# CN-Cape004.net
KiCad netlist of a schematic drawn in EAGLE
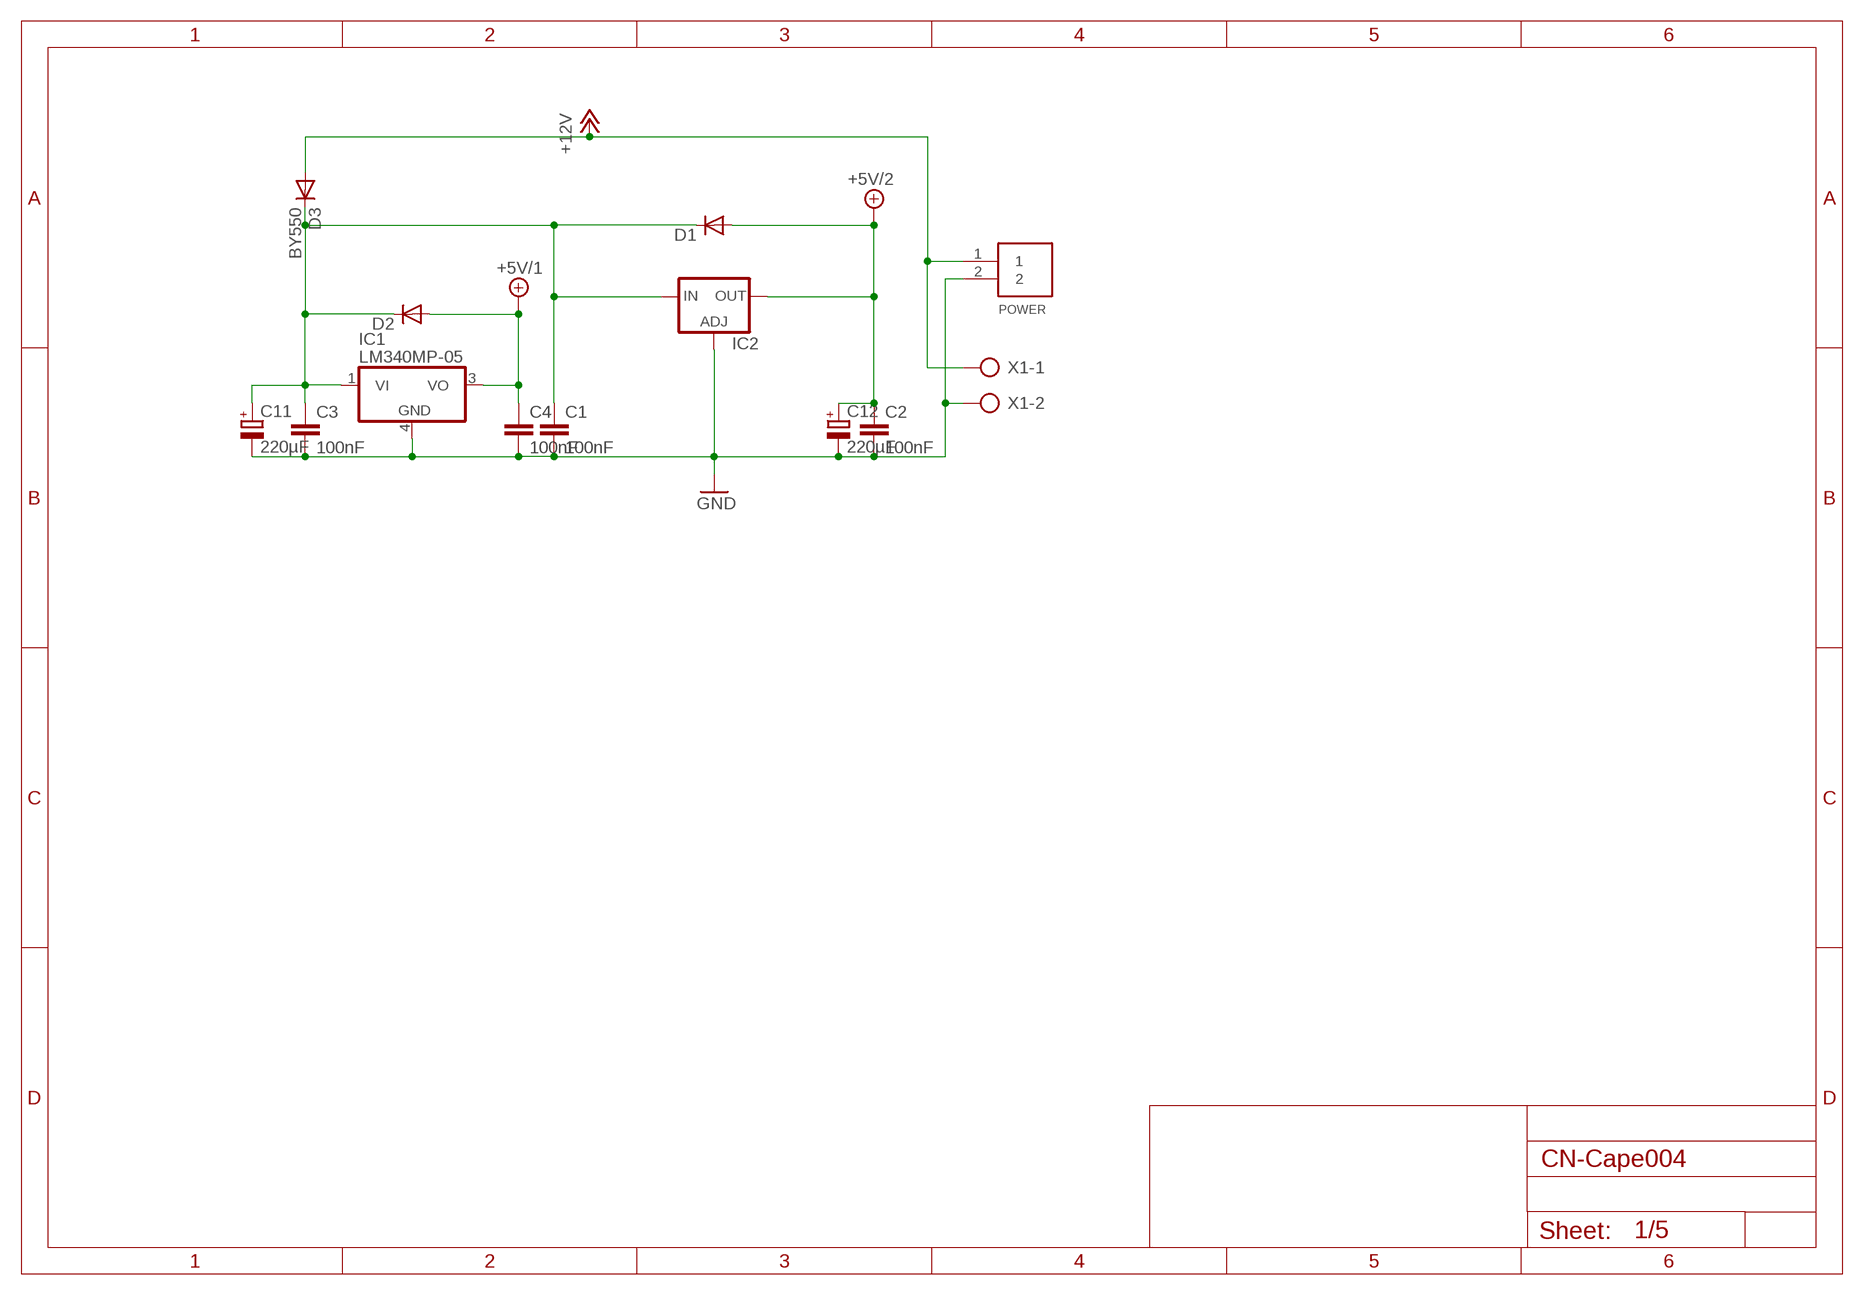
[diagram p0: schematic, sheet 1]
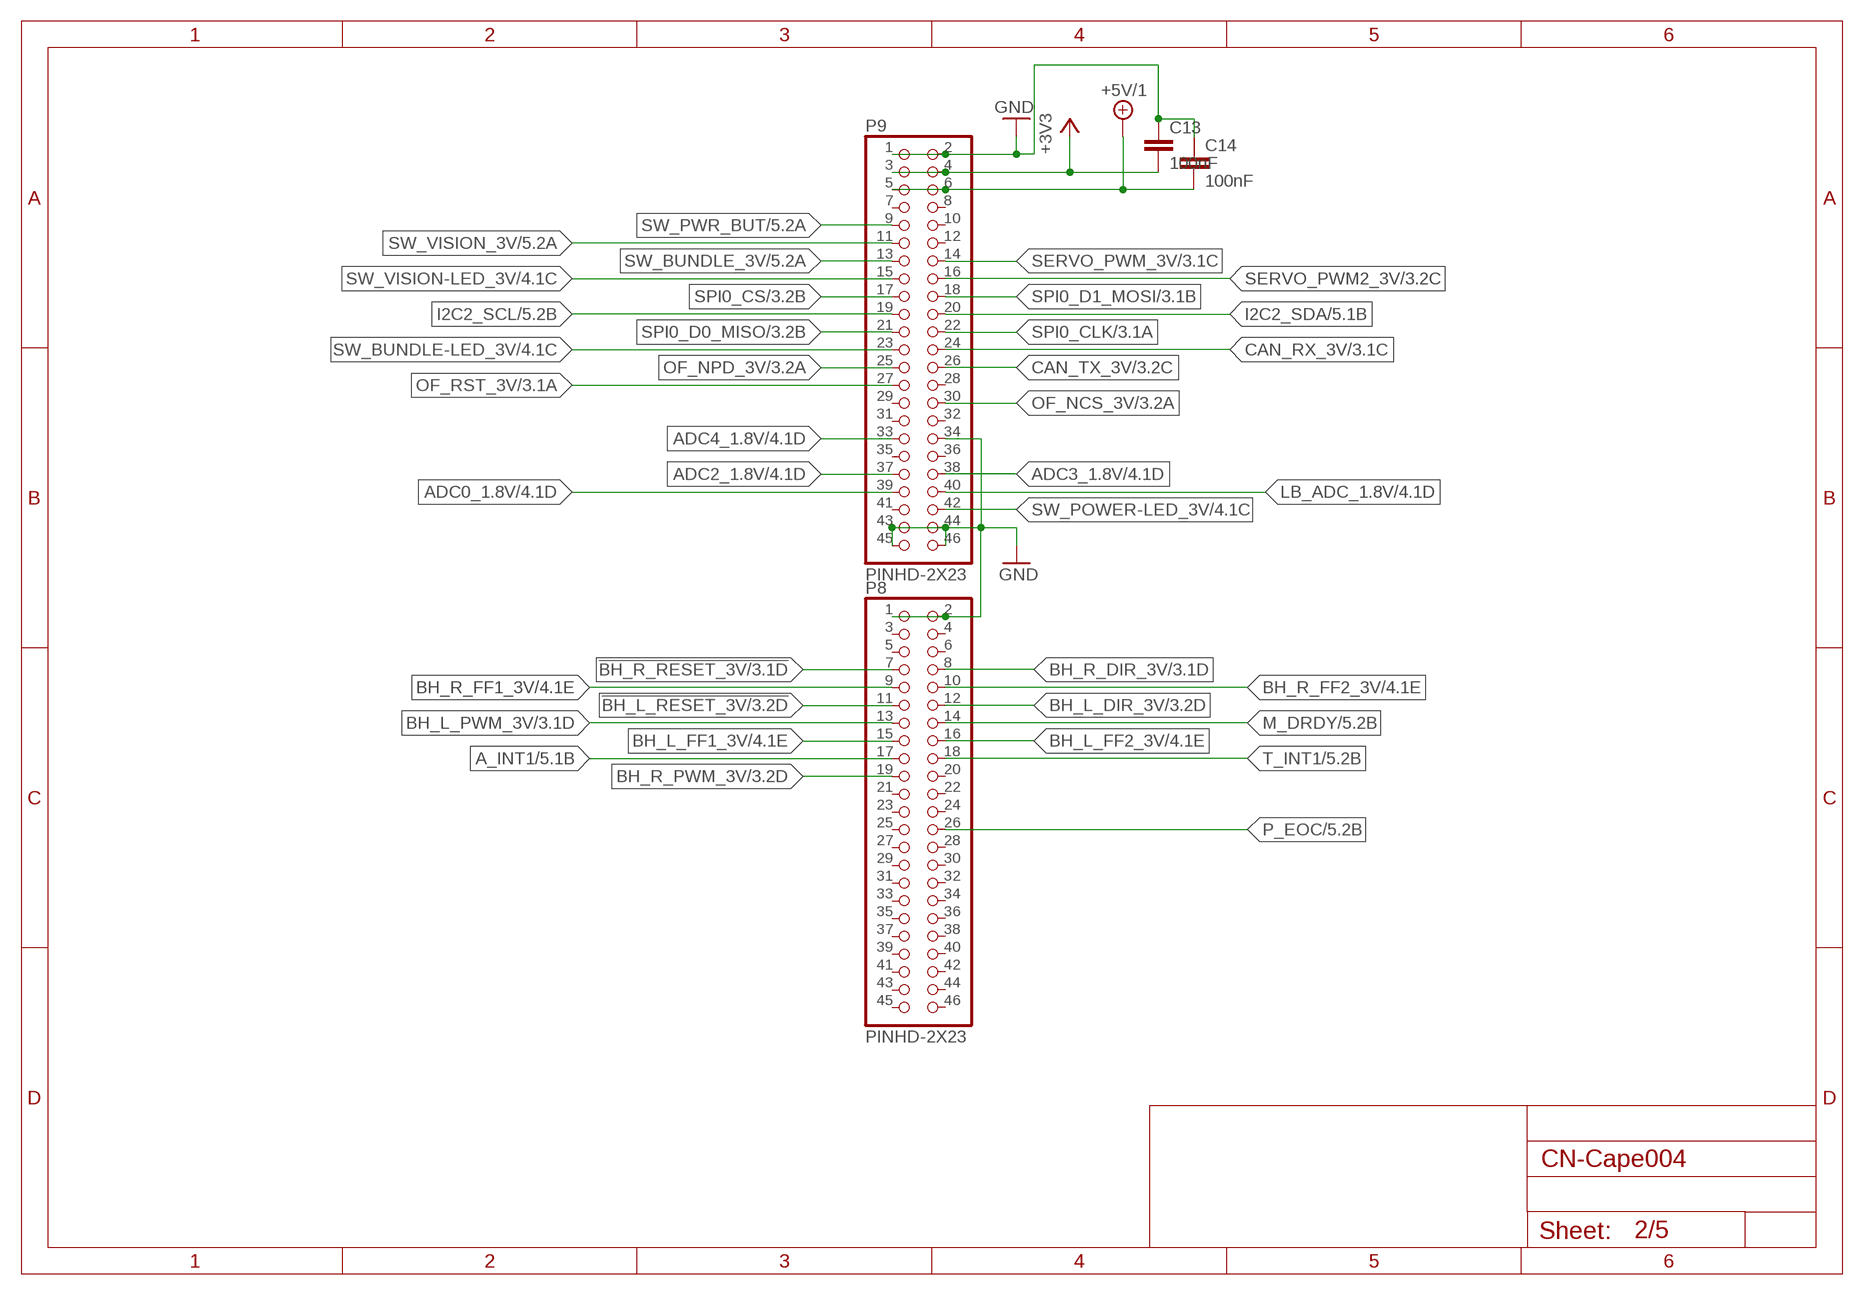
[diagram p1: schematic, sheet 2]
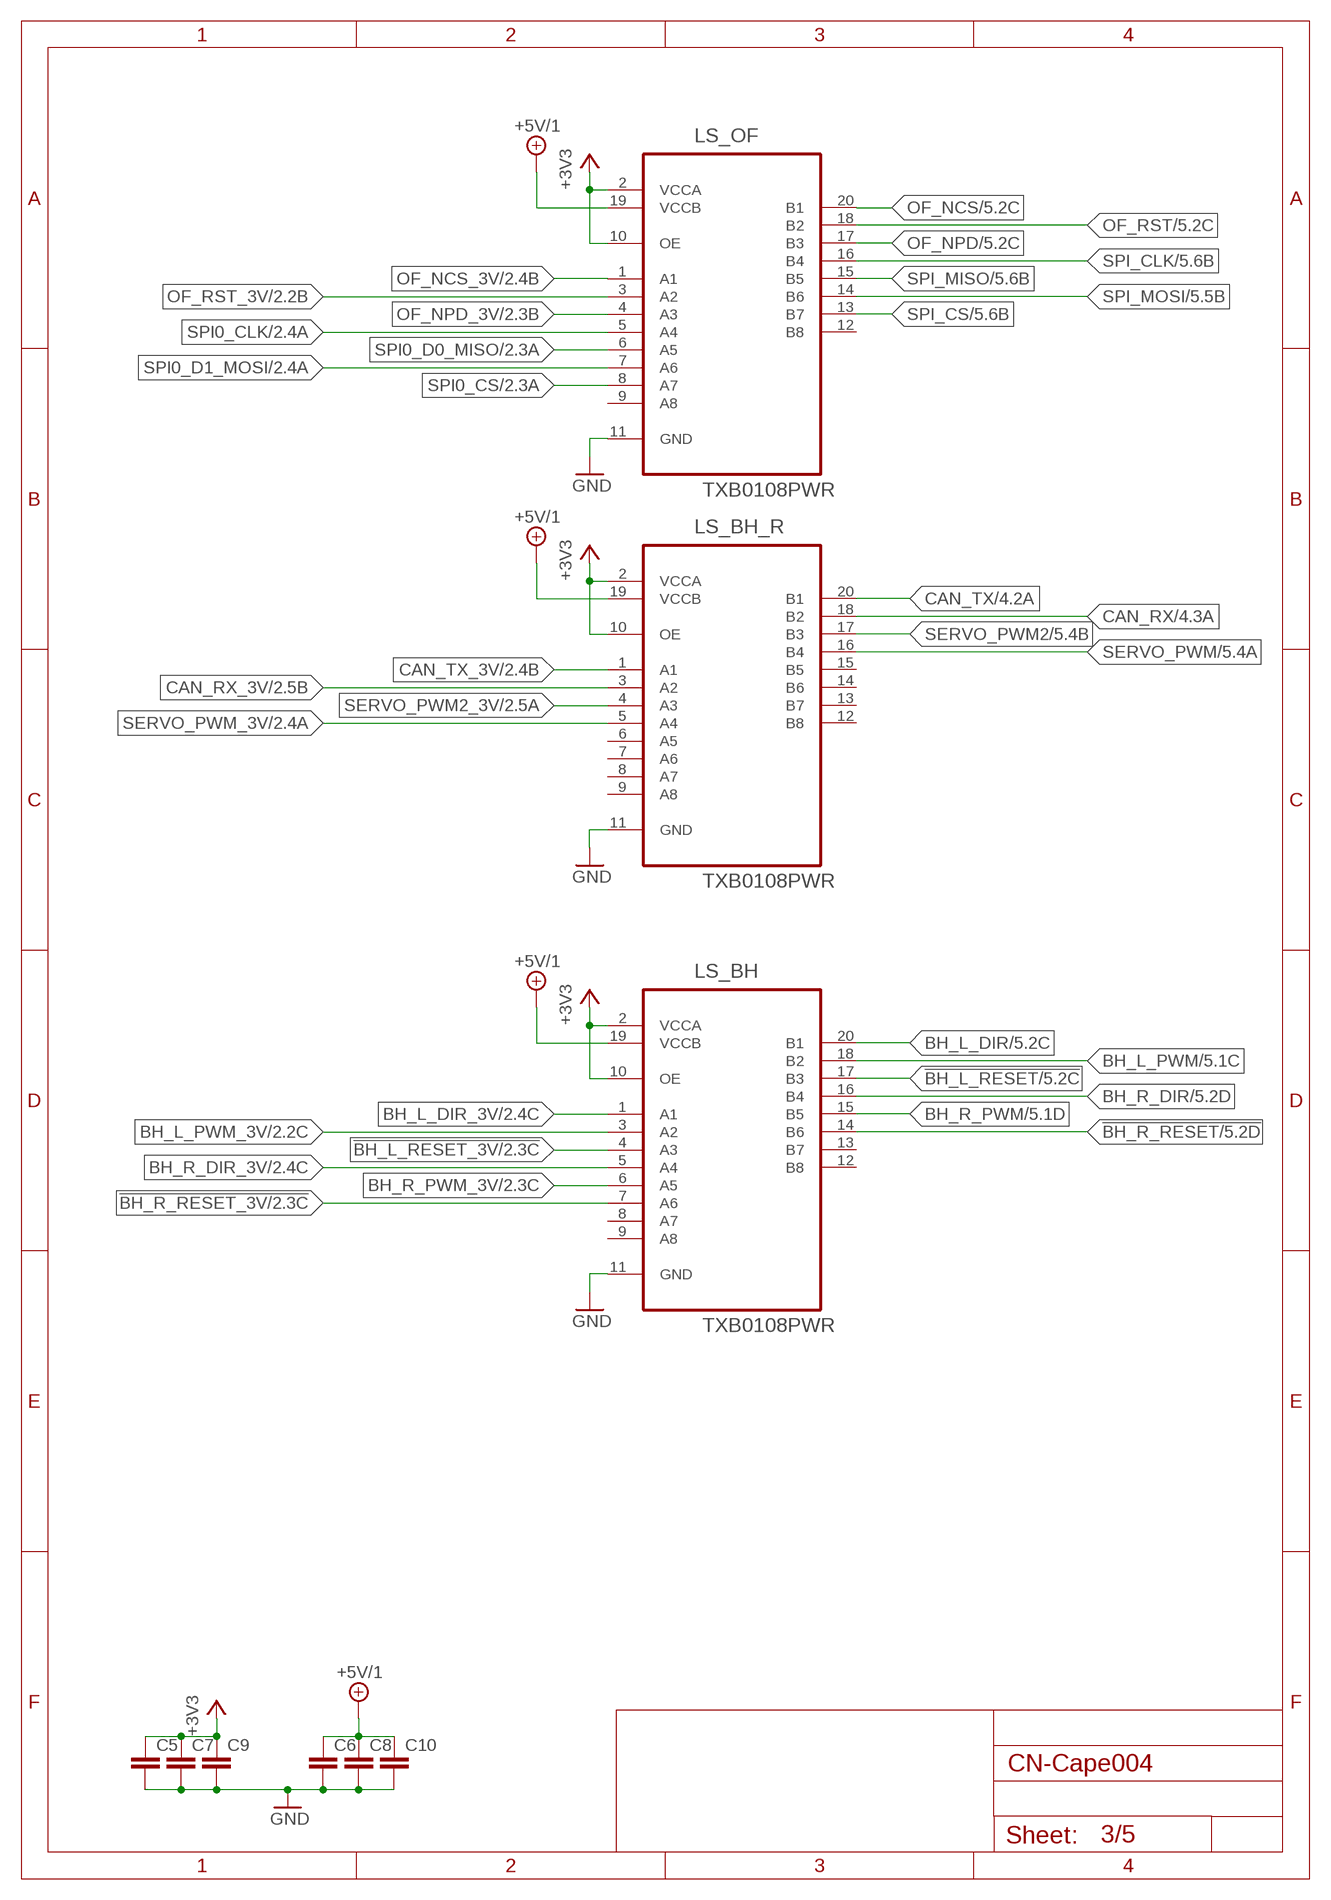
[diagram p2: schematic, sheet 3]
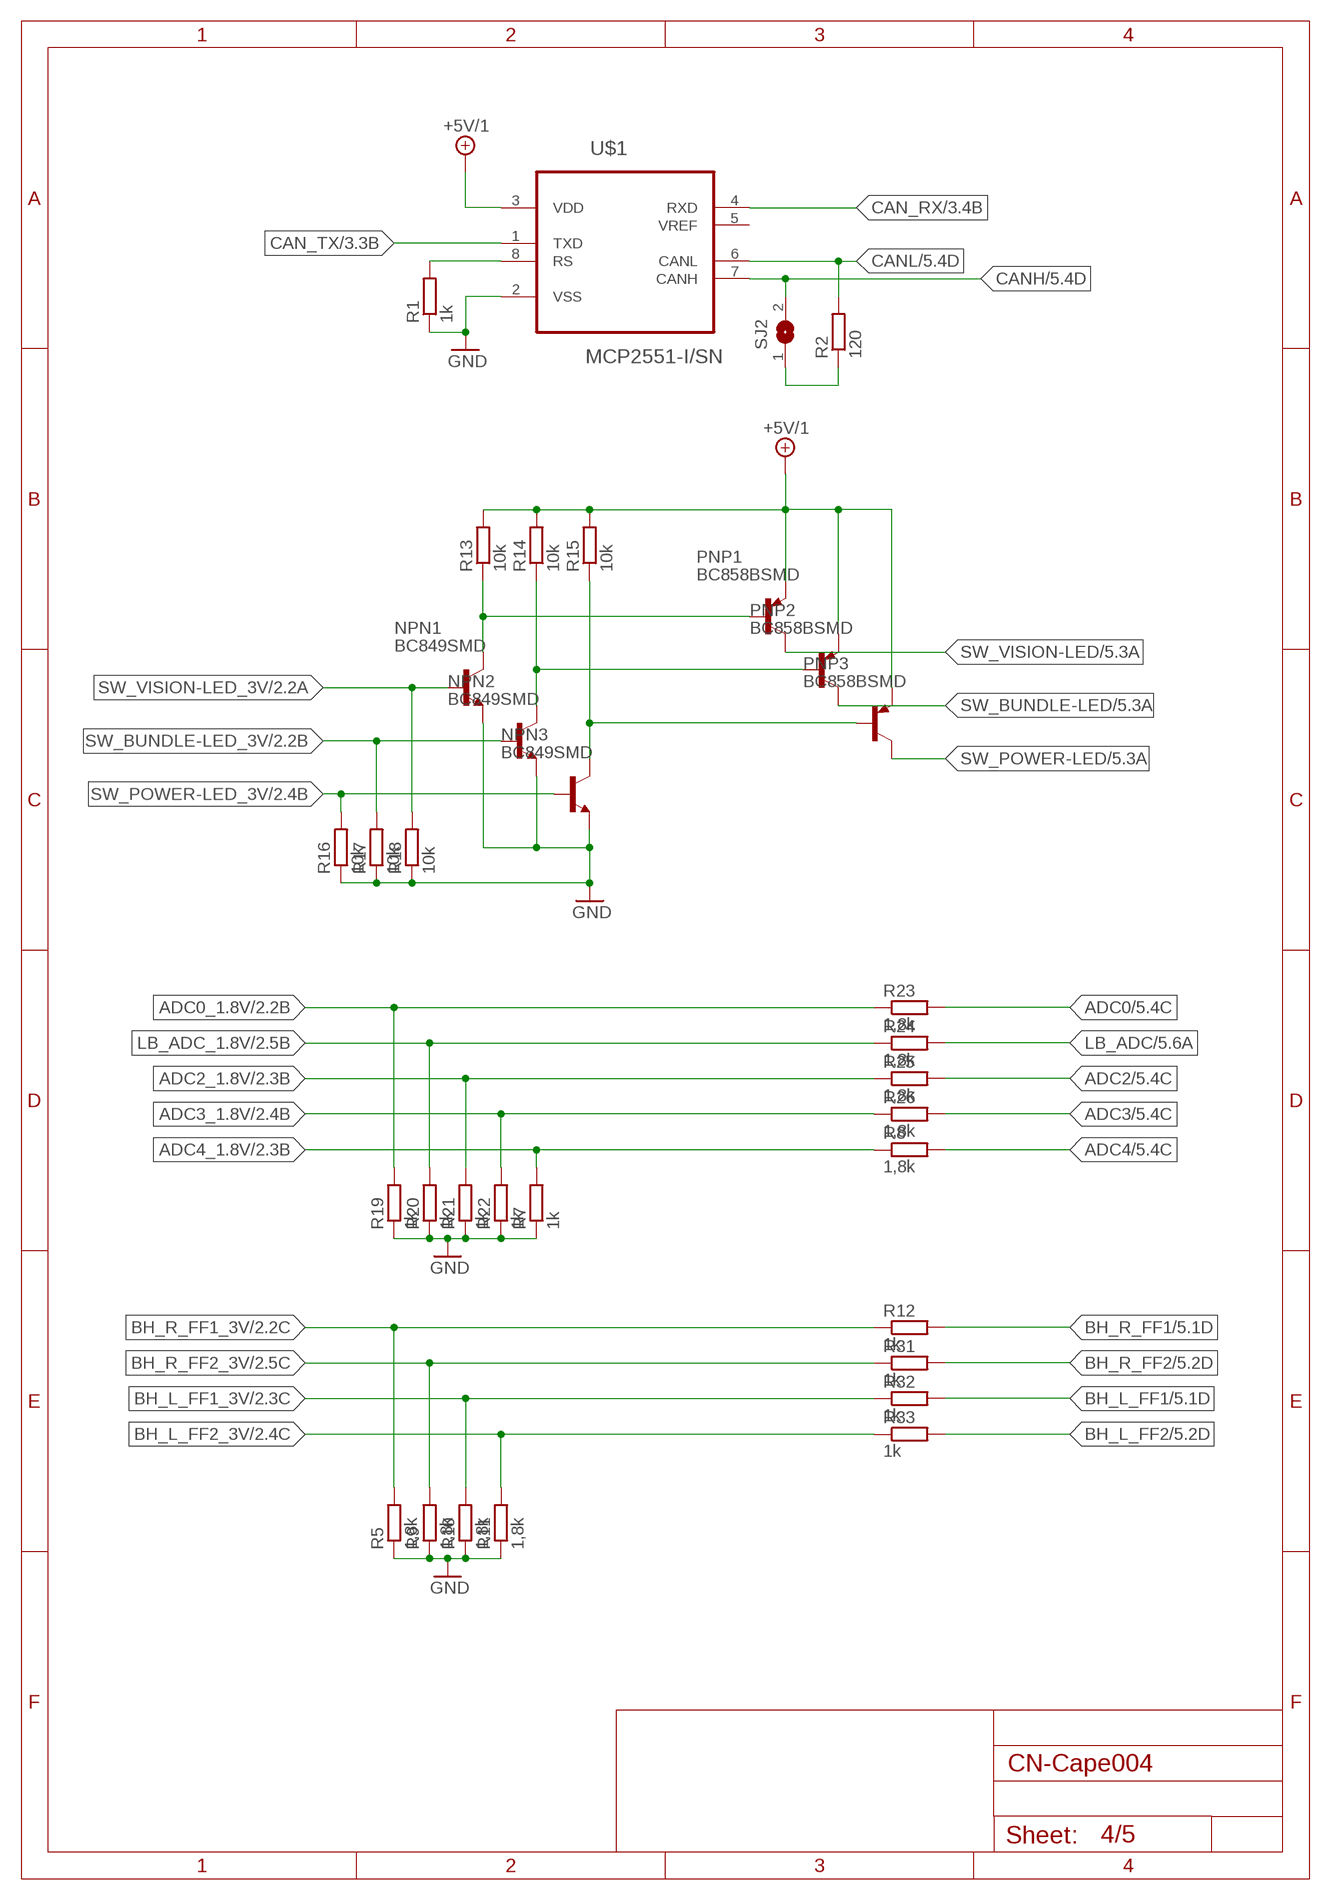
[diagram p3: schematic, sheet 4]
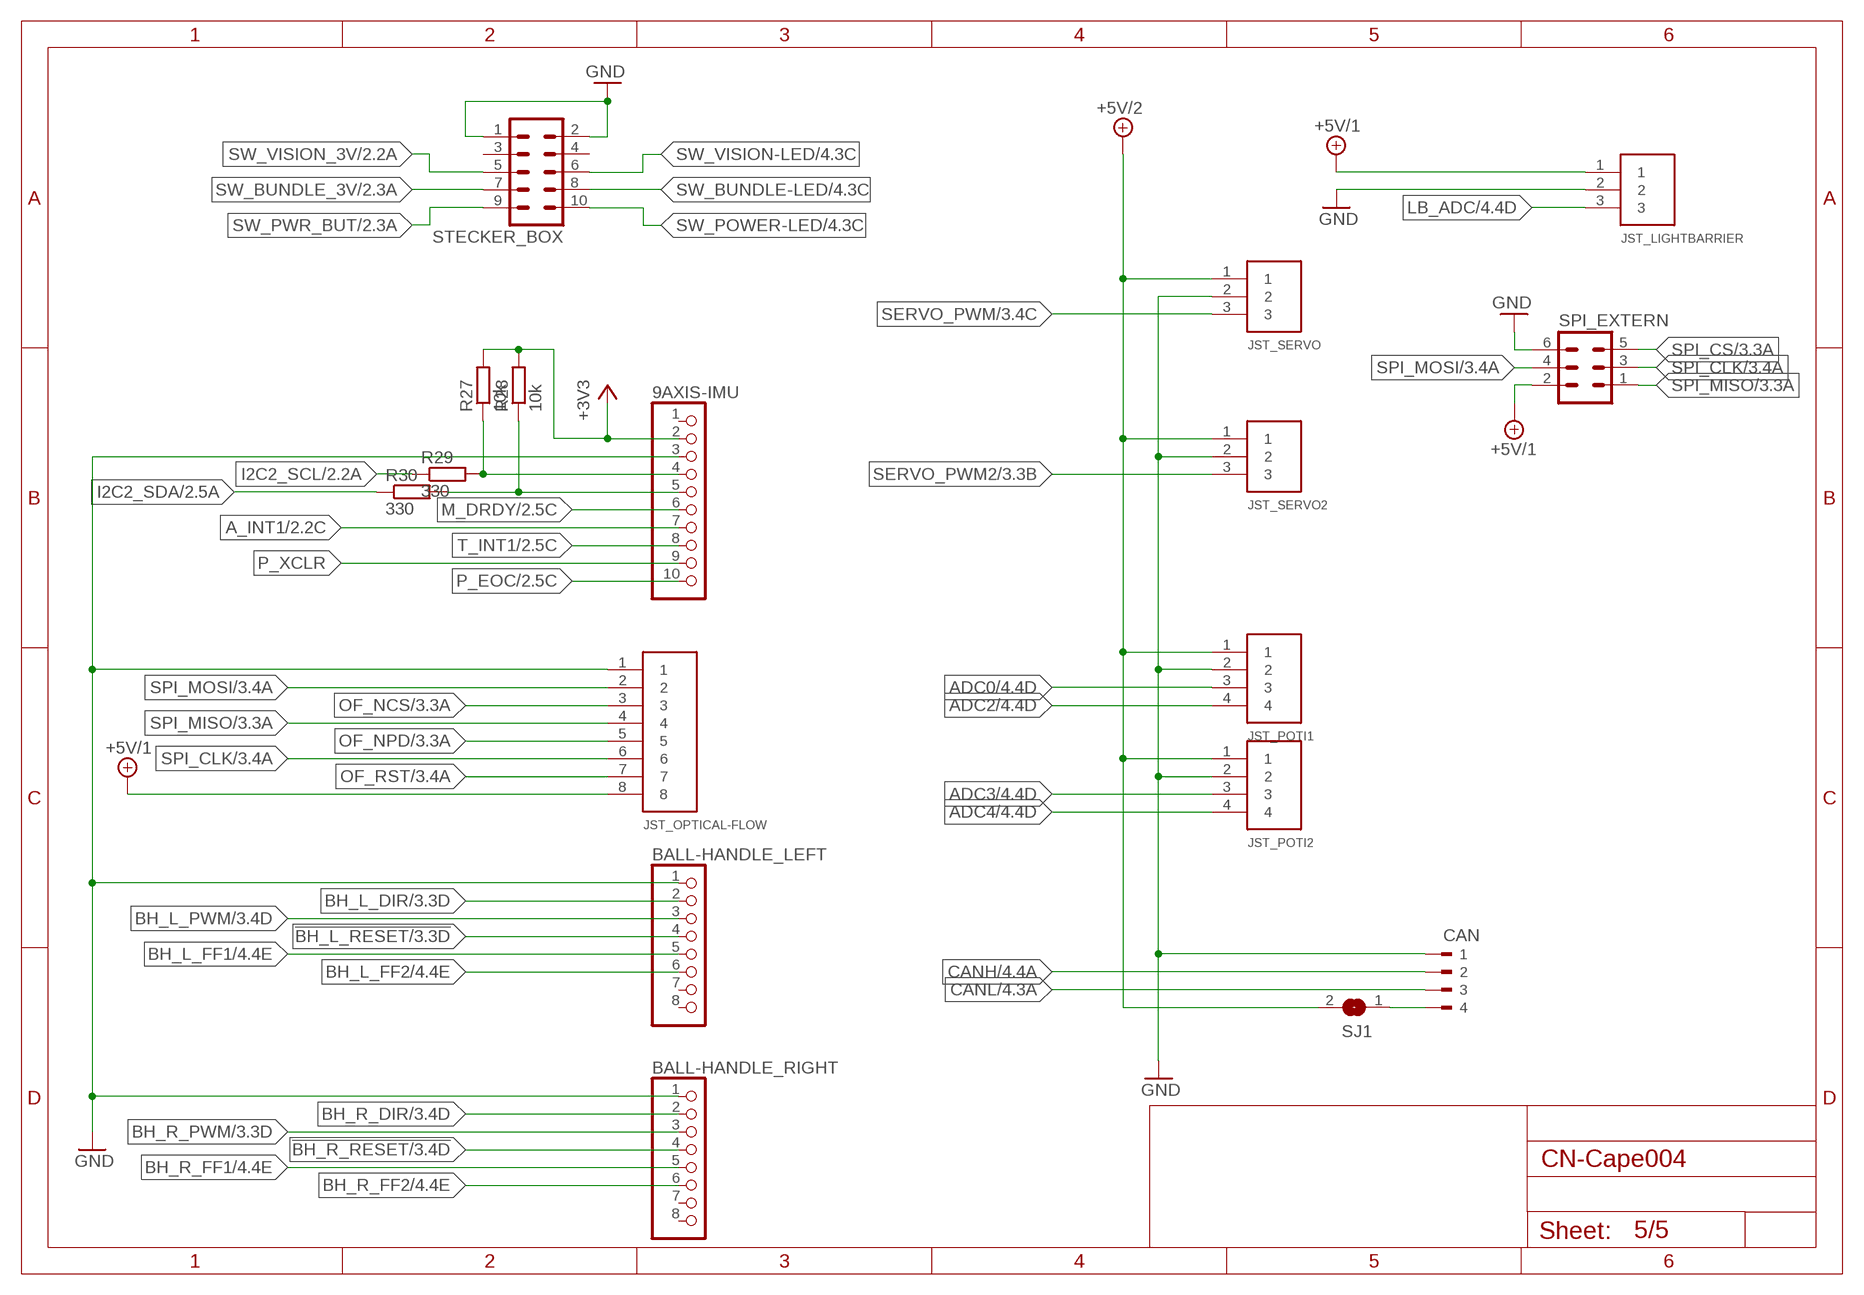
[diagram p4: schematic, sheet 5]

(export (version "E")
  (design (tool "Eeschema 10.0.6"))
  (components
    (comp (ref "C1")
      (value "100nF")
      (footprint "eagle-import:C0603")
      (libsource (lib "eagle-import") (part "C-EUC0603"))
    )
    (comp (ref "C2")
      (value "100nF")
      (footprint "eagle-import:C0603")
      (libsource (lib "eagle-import") (part "C-EUC0603"))
    )
    (comp (ref "C3")
      (value "100nF")
      (footprint "eagle-import:C0603")
      (libsource (lib "eagle-import") (part "C-EUC0603"))
    )
    (comp (ref "C4")
      (value "100nF")
      (footprint "eagle-import:C0603")
      (libsource (lib "eagle-import") (part "C-EUC0603"))
    )
    (comp (ref "C11")
      (value "220µF")
      (footprint "eagle-import:E3,5-8")
      (libsource (lib "eagle-import") (part "CPOL-EUE3.5-8"))
    )
    (comp (ref "C12")
      (value "220µF")
      (footprint "eagle-import:E3,5-8")
      (libsource (lib "eagle-import") (part "CPOL-EUE3.5-8"))
    )
    (comp (ref "D1")
      (value "DIODE-SOD123")
      (footprint "eagle-import:SOD123")
      (libsource (lib "eagle-import") (part "DIODE-SOD123"))
    )
    (comp (ref "D2")
      (value "DIODE-SOD123")
      (footprint "eagle-import:SOD123")
      (libsource (lib "eagle-import") (part "DIODE-SOD123"))
    )
    (comp (ref "D3")
      (value "BY550")
      (footprint "eagle-import:DO27-15")
      (libsource (lib "eagle-import") (part "BY550"))
    )
    (comp (ref "IC1")
      (value "LM340MP-05")
      (footprint "eagle-import:SOT223")
      (libsource (lib "eagle-import") (part "LM340?-MP05"))
    )
    (comp (ref "IC2")
      (value "LM138-TL")
      (footprint "eagle-import:TO220L1")
      (libsource (lib "eagle-import") (part "LM138-TL"))
    )
    (comp (ref "POWER")
      (value "S2PIN")
      (footprint "eagle-import:S2B-EH")
      (libsource (lib "eagle-import") (part "S2PIN"))
    )
    (comp (ref "X1")
      (value "AK500/2-H")
      (footprint "eagle-import:AK500_2-H")
      (libsource (lib "eagle-import") (part "AK500/2-H"))
    )
    (comp (ref "C13")
      (value "100nF")
      (footprint "eagle-import:C0603")
      (libsource (lib "eagle-import") (part "C-EUC0603"))
    )
    (comp (ref "C14")
      (value "100nF")
      (footprint "eagle-import:C0603")
      (libsource (lib "eagle-import") (part "C-EUC0603"))
    )
    (comp (ref "P8")
      (value "PINHD-2X23")
      (footprint "eagle-import:2X23")
      (libsource (lib "eagle-import") (part "PINHD-2X23"))
    )
    (comp (ref "P9")
      (value "PINHD-2X23")
      (footprint "eagle-import:2X23")
      (libsource (lib "eagle-import") (part "PINHD-2X23"))
    )
    (comp (ref "9AXIS-IMU")
      (value "PINHD-1X10")
      (footprint "eagle-import:1X10")
      (libsource (lib "eagle-import") (part "PINHD-1X10"))
    )
    (comp (ref "BALL-HANDLE_LEFT")
      (value "PINHD-1X8")
      (footprint "eagle-import:1X08")
      (libsource (lib "eagle-import") (part "PINHD-1X8"))
    )
    (comp (ref "BALL-HANDLE_RIGHT")
      (value "PINHD-1X8")
      (footprint "eagle-import:1X08")
      (libsource (lib "eagle-import") (part "PINHD-1X8"))
    )
    (comp (ref "CAN")
      (value "90-4")
      (footprint "eagle-import:90-4")
      (libsource (lib "eagle-import") (part "90-4"))
    )
    (comp (ref "JST_LIGHTBARRIER")
      (value "S3PIN")
      (footprint "eagle-import:S3B-EH")
      (libsource (lib "eagle-import") (part "S3PIN"))
    )
    (comp (ref "JST_OPTICAL-FLOW")
      (value "S8PIN")
      (footprint "eagle-import:S8B-EH")
      (libsource (lib "eagle-import") (part "S8PIN"))
    )
    (comp (ref "JST_POTI1")
      (value "4PIN")
      (footprint "eagle-import:B4B-EH")
      (libsource (lib "eagle-import") (part "4PIN"))
    )
    (comp (ref "JST_POTI2")
      (value "4PIN")
      (footprint "eagle-import:B4B-EH")
      (libsource (lib "eagle-import") (part "4PIN"))
    )
    (comp (ref "JST_SERVO")
      (value "S3PIN")
      (footprint "eagle-import:S3B-EH")
      (libsource (lib "eagle-import") (part "S3PIN"))
    )
    (comp (ref "JST_SERVO2")
      (value "3PIN")
      (footprint "eagle-import:B3B-EH")
      (libsource (lib "eagle-import") (part "3PIN"))
    )
    (comp (ref "R27")
      (value "10k")
      (footprint "eagle-import:R0805")
      (libsource (lib "eagle-import") (part "R-EU_R0805"))
    )
    (comp (ref "R28")
      (value "10k")
      (footprint "eagle-import:R0805")
      (libsource (lib "eagle-import") (part "R-EU_R0805"))
    )
    (comp (ref "R29")
      (value "330")
      (footprint "eagle-import:R0805")
      (libsource (lib "eagle-import") (part "R-EU_R0805"))
    )
    (comp (ref "R30")
      (value "330")
      (footprint "eagle-import:R0805")
      (libsource (lib "eagle-import") (part "R-EU_R0805"))
    )
    (comp (ref "SJ1") (value "SJ") (footprint "eagle-import:SJ") (libsource (lib "eagle-import") (part "SJ")))
    (comp (ref "SPI_EXTERN")
      (value "ML6")
      (footprint "eagle-import:ML6")
      (libsource (lib "eagle-import") (part "ML6"))
    )
    (comp (ref "STECKER_BOX")
      (value "ML10")
      (footprint "eagle-import:ML10")
      (libsource (lib "eagle-import") (part "ML10"))
    )
    (comp (ref "C5")
      (value "C-EUC0603")
      (footprint "eagle-import:C0603")
      (libsource (lib "eagle-import") (part "C-EUC0603"))
    )
    (comp (ref "C6")
      (value "C-EUC0603")
      (footprint "eagle-import:C0603")
      (libsource (lib "eagle-import") (part "C-EUC0603"))
    )
    (comp (ref "C7")
      (value "C-EUC0603")
      (footprint "eagle-import:C0603")
      (libsource (lib "eagle-import") (part "C-EUC0603"))
    )
    (comp (ref "C8")
      (value "C-EUC0603")
      (footprint "eagle-import:C0603")
      (libsource (lib "eagle-import") (part "C-EUC0603"))
    )
    (comp (ref "C9")
      (value "C-EUC0603")
      (footprint "eagle-import:C0603")
      (libsource (lib "eagle-import") (part "C-EUC0603"))
    )
    (comp (ref "C10")
      (value "C-EUC0603")
      (footprint "eagle-import:C0603")
      (libsource (lib "eagle-import") (part "C-EUC0603"))
    )
    (comp (ref "LS_BH")
      (value "TXB0108PWR")
      (footprint "eagle-import:SOP65P640X120-20N")
      (libsource (lib "eagle-import") (part "TXB0108PWR"))
    )
    (comp (ref "LS_BH_R")
      (value "TXB0108PWR")
      (footprint "eagle-import:SOP65P640X120-20N")
      (libsource (lib "eagle-import") (part "TXB0108PWR"))
    )
    (comp (ref "LS_OF")
      (value "TXB0108PWR")
      (footprint "eagle-import:SOP65P640X120-20N")
      (libsource (lib "eagle-import") (part "TXB0108PWR"))
    )
    (comp (ref "NPN1")
      (value "BC849SMD")
      (footprint "eagle-import:SOT23-BEC")
      (libsource (lib "eagle-import") (part "BC849SMD"))
    )
    (comp (ref "NPN2")
      (value "BC849SMD")
      (footprint "eagle-import:SOT23-BEC")
      (libsource (lib "eagle-import") (part "BC849SMD"))
    )
    (comp (ref "NPN3")
      (value "BC849SMD")
      (footprint "eagle-import:SOT23-BEC")
      (libsource (lib "eagle-import") (part "BC849SMD"))
    )
    (comp (ref "PNP1")
      (value "BC858BSMD")
      (footprint "eagle-import:SOT23-BEC")
      (libsource (lib "eagle-import") (part "BC858SMDB"))
    )
    (comp (ref "PNP2")
      (value "BC858BSMD")
      (footprint "eagle-import:SOT23-BEC")
      (libsource (lib "eagle-import") (part "BC858SMDB"))
    )
    (comp (ref "PNP3")
      (value "BC858BSMD")
      (footprint "eagle-import:SOT23-BEC")
      (libsource (lib "eagle-import") (part "BC858SMDB"))
    )
    (comp (ref "R1")
      (value "1k")
      (footprint "eagle-import:R0805")
      (libsource (lib "eagle-import") (part "R-EU_R0805"))
    )
    (comp (ref "R2")
      (value "120")
      (footprint "eagle-import:R0805")
      (libsource (lib "eagle-import") (part "R-EU_R0805"))
    )
    (comp (ref "R5")
      (value "1,8k")
      (footprint "eagle-import:R0805")
      (libsource (lib "eagle-import") (part "R-EU_R0805"))
    )
    (comp (ref "R7")
      (value "1k")
      (footprint "eagle-import:R0805")
      (libsource (lib "eagle-import") (part "R-EU_R0805"))
    )
    (comp (ref "R8")
      (value "1,8k")
      (footprint "eagle-import:R0805")
      (libsource (lib "eagle-import") (part "R-EU_R0805"))
    )
    (comp (ref "R9")
      (value "1,8k")
      (footprint "eagle-import:R0805")
      (libsource (lib "eagle-import") (part "R-EU_R0805"))
    )
    (comp (ref "R10")
      (value "1,8k")
      (footprint "eagle-import:R0805")
      (libsource (lib "eagle-import") (part "R-EU_R0805"))
    )
    (comp (ref "R11")
      (value "1,8k")
      (footprint "eagle-import:R0805")
      (libsource (lib "eagle-import") (part "R-EU_R0805"))
    )
    (comp (ref "R12")
      (value "1k")
      (footprint "eagle-import:R0805")
      (libsource (lib "eagle-import") (part "R-EU_R0805"))
    )
    (comp (ref "R13")
      (value "10k")
      (footprint "eagle-import:R0805")
      (libsource (lib "eagle-import") (part "R-EU_R0805"))
    )
    (comp (ref "R14")
      (value "10k")
      (footprint "eagle-import:R0805")
      (libsource (lib "eagle-import") (part "R-EU_R0805"))
    )
    (comp (ref "R15")
      (value "10k")
      (footprint "eagle-import:R0805")
      (libsource (lib "eagle-import") (part "R-EU_R0805"))
    )
    (comp (ref "R16")
      (value "10k")
      (footprint "eagle-import:R0805")
      (libsource (lib "eagle-import") (part "R-EU_R0805"))
    )
    (comp (ref "R17")
      (value "10k")
      (footprint "eagle-import:R0805")
      (libsource (lib "eagle-import") (part "R-EU_R0805"))
    )
    (comp (ref "R18")
      (value "10k")
      (footprint "eagle-import:R0805")
      (libsource (lib "eagle-import") (part "R-EU_R0805"))
    )
    (comp (ref "R19")
      (value "1k")
      (footprint "eagle-import:R0805")
      (libsource (lib "eagle-import") (part "R-EU_R0805"))
    )
    (comp (ref "R20")
      (value "1k")
      (footprint "eagle-import:R0805")
      (libsource (lib "eagle-import") (part "R-EU_R0805"))
    )
    (comp (ref "R21")
      (value "1k")
      (footprint "eagle-import:R0805")
      (libsource (lib "eagle-import") (part "R-EU_R0805"))
    )
    (comp (ref "R22")
      (value "1k")
      (footprint "eagle-import:R0805")
      (libsource (lib "eagle-import") (part "R-EU_R0805"))
    )
    (comp (ref "R23")
      (value "1,8k")
      (footprint "eagle-import:R0805")
      (libsource (lib "eagle-import") (part "R-EU_R0805"))
    )
    (comp (ref "R24")
      (value "1,8k")
      (footprint "eagle-import:R0805")
      (libsource (lib "eagle-import") (part "R-EU_R0805"))
    )
    (comp (ref "R25")
      (value "1,8k")
      (footprint "eagle-import:R0805")
      (libsource (lib "eagle-import") (part "R-EU_R0805"))
    )
    (comp (ref "R26")
      (value "1,8k")
      (footprint "eagle-import:R0805")
      (libsource (lib "eagle-import") (part "R-EU_R0805"))
    )
    (comp (ref "R31")
      (value "1k")
      (footprint "eagle-import:R0805")
      (libsource (lib "eagle-import") (part "R-EU_R0805"))
    )
    (comp (ref "R32")
      (value "1k")
      (footprint "eagle-import:R0805")
      (libsource (lib "eagle-import") (part "R-EU_R0805"))
    )
    (comp (ref "R33")
      (value "1k")
      (footprint "eagle-import:R0805")
      (libsource (lib "eagle-import") (part "R-EU_R0805"))
    )
    (comp (ref "SJ2") (value "SJ") (footprint "eagle-import:SJ") (libsource (lib "eagle-import") (part "SJ")))
    (comp (ref "U$1")
      (value "MCP2551-I/SN")
      (footprint "eagle-import:SOIC127P600X175-8N")
      (libsource (lib "eagle-import") (part "MCP2551-I/SN"))
    )
  )
  (nets
    (net (code "1") (name "+3V3") (class "Default")
      (node (ref "9AXIS-IMU") (pin "2") (pinfunction "2_2") (pintype "passive"))
      (node (ref "C13") (pin "2") (pinfunction "2_2") (pintype "passive"))
      (node (ref "C5") (pin "1") (pinfunction "1_1") (pintype "passive"))
      (node (ref "C7") (pin "1") (pinfunction "1_1") (pintype "passive"))
      (node (ref "C9") (pin "1") (pinfunction "1_1") (pintype "passive"))
      (node (ref "LS_BH") (pin "10") (pinfunction "OE_10") (pintype "input"))
      (node (ref "LS_BH") (pin "2") (pinfunction "VCCA_2") (pintype "power_in"))
      (node (ref "LS_BH_R") (pin "10") (pinfunction "OE_10") (pintype "input"))
      (node (ref "LS_BH_R") (pin "2") (pinfunction "VCCA_2") (pintype "power_in"))
      (node (ref "LS_OF") (pin "10") (pinfunction "OE_10") (pintype "input"))
      (node (ref "LS_OF") (pin "2") (pinfunction "VCCA_2") (pintype "power_in"))
      (node (ref "P9") (pin "3") (pinfunction "3_3") (pintype "passive"))
      (node (ref "P9") (pin "4") (pinfunction "4_4") (pintype "passive"))
      (node (ref "R27") (pin "2") (pinfunction "2_2") (pintype "passive"))
      (node (ref "R28") (pin "2") (pinfunction "2_2") (pintype "passive"))
    )
    (net (code "2") (name "+5V{slash}1") (class "Default")
      (node (ref "C10") (pin "1") (pinfunction "1_1") (pintype "passive"))
      (node (ref "C14") (pin "2") (pinfunction "2_2") (pintype "passive"))
      (node (ref "C4") (pin "1") (pinfunction "1_1") (pintype "passive"))
      (node (ref "C6") (pin "1") (pinfunction "1_1") (pintype "passive"))
      (node (ref "C8") (pin "1") (pinfunction "1_1") (pintype "passive"))
      (node (ref "D2") (pin "A") (pinfunction "A_A") (pintype "passive"))
      (node (ref "IC1") (pin "3") (pinfunction "VO_3") (pintype "passive"))
      (node (ref "JST_LIGHTBARRIER") (pin "1") (pinfunction "1_1") (pintype "bidirectional"))
      (node (ref "JST_OPTICAL-FLOW") (pin "8") (pinfunction "8_8") (pintype "bidirectional"))
      (node (ref "LS_BH") (pin "19") (pinfunction "VCCB_19") (pintype "power_in"))
      (node (ref "LS_BH_R") (pin "19") (pinfunction "VCCB_19") (pintype "power_in"))
      (node (ref "LS_OF") (pin "19") (pinfunction "VCCB_19") (pintype "power_in"))
      (node (ref "P9") (pin "5") (pinfunction "5_5") (pintype "passive"))
      (node (ref "P9") (pin "6") (pinfunction "6_6") (pintype "passive"))
      (node (ref "PNP1") (pin "E") (pinfunction "E_E") (pintype "passive"))
      (node (ref "PNP2") (pin "E") (pinfunction "E_E") (pintype "passive"))
      (node (ref "PNP3") (pin "E") (pinfunction "E_E") (pintype "passive"))
      (node (ref "R13") (pin "2") (pinfunction "2_2") (pintype "passive"))
      (node (ref "R14") (pin "2") (pinfunction "2_2") (pintype "passive"))
      (node (ref "R15") (pin "2") (pinfunction "2_2") (pintype "passive"))
      (node (ref "SPI_EXTERN") (pin "2") (pinfunction "2_2") (pintype "passive"))
      (node (ref "U$1") (pin "3") (pinfunction "VDD_3") (pintype "power_in"))
    )
    (net (code "3") (name "+5V{slash}2") (class "Default")
      (node (ref "C12") (pin "+") (pinfunction "+_+") (pintype "passive"))
      (node (ref "C2") (pin "1") (pinfunction "1_1") (pintype "passive"))
      (node (ref "D1") (pin "A") (pinfunction "A_A") (pintype "passive"))
      (node (ref "IC2") (pin "2") (pinfunction "OUT_2") (pintype "passive"))
      (node (ref "JST_POTI1") (pin "1") (pinfunction "1_1") (pintype "bidirectional"))
      (node (ref "JST_POTI2") (pin "1") (pinfunction "1_1") (pintype "bidirectional"))
      (node (ref "JST_SERVO") (pin "1") (pinfunction "1_1") (pintype "bidirectional"))
      (node (ref "JST_SERVO2") (pin "1") (pinfunction "1_1") (pintype "bidirectional"))
      (node (ref "SJ1") (pin "2") (pinfunction "2_2") (pintype "passive"))
    )
    (net (code "4") (name "+12V") (class "Default")
      (node (ref "D3") (pin "A") (pinfunction "A_A") (pintype "passive"))
      (node (ref "POWER") (pin "1") (pinfunction "1_1") (pintype "bidirectional"))
      (node (ref "X1") (pin "1") (pinfunction "KL_1") (pintype "passive"))
    )
    (net (code "5") (name "ADC0") (class "Default")
      (node (ref "JST_POTI1") (pin "3") (pinfunction "3_3") (pintype "bidirectional"))
      (node (ref "R23") (pin "2") (pinfunction "2_2") (pintype "passive"))
    )
    (net (code "6") (name "ADC0_1.8V") (class "Default")
      (node (ref "P9") (pin "39") (pinfunction "39_39") (pintype "passive"))
      (node (ref "R19") (pin "2") (pinfunction "2_2") (pintype "passive"))
      (node (ref "R23") (pin "1") (pinfunction "1_1") (pintype "passive"))
    )
    (net (code "7") (name "ADC2") (class "Default")
      (node (ref "JST_POTI1") (pin "4") (pinfunction "4_4") (pintype "bidirectional"))
      (node (ref "R25") (pin "2") (pinfunction "2_2") (pintype "passive"))
    )
    (net (code "8") (name "ADC2_1.8V") (class "Default")
      (node (ref "P9") (pin "37") (pinfunction "37_37") (pintype "passive"))
      (node (ref "R21") (pin "2") (pinfunction "2_2") (pintype "passive"))
      (node (ref "R25") (pin "1") (pinfunction "1_1") (pintype "passive"))
    )
    (net (code "9") (name "ADC3") (class "Default")
      (node (ref "JST_POTI2") (pin "3") (pinfunction "3_3") (pintype "bidirectional"))
      (node (ref "R26") (pin "2") (pinfunction "2_2") (pintype "passive"))
    )
    (net (code "10") (name "ADC3_1.8V") (class "Default")
      (node (ref "P9") (pin "38") (pinfunction "38_38") (pintype "passive"))
      (node (ref "R22") (pin "2") (pinfunction "2_2") (pintype "passive"))
      (node (ref "R26") (pin "1") (pinfunction "1_1") (pintype "passive"))
    )
    (net (code "11") (name "ADC4") (class "Default")
      (node (ref "JST_POTI2") (pin "4") (pinfunction "4_4") (pintype "bidirectional"))
      (node (ref "R8") (pin "2") (pinfunction "2_2") (pintype "passive"))
    )
    (net (code "12") (name "ADC4_1.8V") (class "Default")
      (node (ref "P9") (pin "33") (pinfunction "33_33") (pintype "passive"))
      (node (ref "R7") (pin "2") (pinfunction "2_2") (pintype "passive"))
      (node (ref "R8") (pin "1") (pinfunction "1_1") (pintype "passive"))
    )
    (net (code "13") (name "A_INT1") (class "Default")
      (node (ref "9AXIS-IMU") (pin "7") (pinfunction "7_7") (pintype "passive"))
      (node (ref "P8") (pin "17") (pinfunction "17_17") (pintype "passive"))
    )
    (net (code "14") (name "BH_L_DIR") (class "Default")
      (node (ref "BALL-HANDLE_LEFT") (pin "2") (pinfunction "2_2") (pintype "passive"))
      (node (ref "LS_BH") (pin "20") (pinfunction "B1_20") (pintype "bidirectional"))
    )
    (net (code "15") (name "BH_L_DIR_3V") (class "Default")
      (node (ref "LS_BH") (pin "1") (pinfunction "A1_1") (pintype "bidirectional"))
      (node (ref "P8") (pin "12") (pinfunction "12_12") (pintype "passive"))
    )
    (net (code "16") (name "BH_L_FF1") (class "Default")
      (node (ref "BALL-HANDLE_LEFT") (pin "5") (pinfunction "5_5") (pintype "passive"))
      (node (ref "R32") (pin "2") (pinfunction "2_2") (pintype "passive"))
    )
    (net (code "17") (name "BH_L_FF1_3V") (class "Default")
      (node (ref "P8") (pin "15") (pinfunction "15_15") (pintype "passive"))
      (node (ref "R10") (pin "2") (pinfunction "2_2") (pintype "passive"))
      (node (ref "R32") (pin "1") (pinfunction "1_1") (pintype "passive"))
    )
    (net (code "18") (name "BH_L_FF2") (class "Default")
      (node (ref "BALL-HANDLE_LEFT") (pin "6") (pinfunction "6_6") (pintype "passive"))
      (node (ref "R33") (pin "2") (pinfunction "2_2") (pintype "passive"))
    )
    (net (code "19") (name "BH_L_FF2_3V") (class "Default")
      (node (ref "P8") (pin "16") (pinfunction "16_16") (pintype "passive"))
      (node (ref "R11") (pin "2") (pinfunction "2_2") (pintype "passive"))
      (node (ref "R33") (pin "1") (pinfunction "1_1") (pintype "passive"))
    )
    (net (code "20") (name "BH_L_PWM") (class "Default")
      (node (ref "BALL-HANDLE_LEFT") (pin "3") (pinfunction "3_3") (pintype "passive"))
      (node (ref "LS_BH") (pin "18") (pinfunction "B2_18") (pintype "bidirectional"))
    )
    (net (code "21") (name "BH_L_PWM_3V") (class "Default")
      (node (ref "LS_BH") (pin "3") (pinfunction "A2_3") (pintype "bidirectional"))
      (node (ref "P8") (pin "13") (pinfunction "13_13") (pintype "passive"))
    )
    (net (code "22") (name "BH_R_DIR") (class "Default")
      (node (ref "BALL-HANDLE_RIGHT") (pin "2") (pinfunction "2_2") (pintype "passive"))
      (node (ref "LS_BH") (pin "16") (pinfunction "B4_16") (pintype "bidirectional"))
    )
    (net (code "23") (name "BH_R_DIR_3V") (class "Default")
      (node (ref "LS_BH") (pin "5") (pinfunction "A4_5") (pintype "bidirectional"))
      (node (ref "P8") (pin "8") (pinfunction "8_8") (pintype "passive"))
    )
    (net (code "24") (name "BH_R_FF1") (class "Default")
      (node (ref "BALL-HANDLE_RIGHT") (pin "5") (pinfunction "5_5") (pintype "passive"))
      (node (ref "R12") (pin "2") (pinfunction "2_2") (pintype "passive"))
    )
    (net (code "25") (name "BH_R_FF1_3V") (class "Default")
      (node (ref "P8") (pin "9") (pinfunction "9_9") (pintype "passive"))
      (node (ref "R12") (pin "1") (pinfunction "1_1") (pintype "passive"))
      (node (ref "R5") (pin "2") (pinfunction "2_2") (pintype "passive"))
    )
    (net (code "26") (name "BH_R_FF2") (class "Default")
      (node (ref "BALL-HANDLE_RIGHT") (pin "6") (pinfunction "6_6") (pintype "passive"))
      (node (ref "R31") (pin "2") (pinfunction "2_2") (pintype "passive"))
    )
    (net (code "27") (name "BH_R_FF2_3V") (class "Default")
      (node (ref "P8") (pin "10") (pinfunction "10_10") (pintype "passive"))
      (node (ref "R31") (pin "1") (pinfunction "1_1") (pintype "passive"))
      (node (ref "R9") (pin "2") (pinfunction "2_2") (pintype "passive"))
    )
    (net (code "28") (name "BH_R_PWM") (class "Default")
      (node (ref "BALL-HANDLE_RIGHT") (pin "3") (pinfunction "3_3") (pintype "passive"))
      (node (ref "LS_BH") (pin "15") (pinfunction "B5_15") (pintype "bidirectional"))
    )
    (net (code "29") (name "BH_R_PWM_3V") (class "Default")
      (node (ref "LS_BH") (pin "6") (pinfunction "A5_6") (pintype "bidirectional"))
      (node (ref "P8") (pin "19") (pinfunction "19_19") (pintype "passive"))
    )
    (net (code "30") (name "CANH") (class "Default")
      (node (ref "CAN") (pin "2") (pinfunction "2_2") (pintype "passive"))
      (node (ref "SJ2") (pin "2") (pinfunction "2_2") (pintype "passive"))
      (node (ref "U$1") (pin "7") (pinfunction "CANH_7") (pintype "bidirectional"))
    )
    (net (code "31") (name "CANL") (class "Default")
      (node (ref "CAN") (pin "3") (pinfunction "3_3") (pintype "passive"))
      (node (ref "R2") (pin "2") (pinfunction "2_2") (pintype "passive"))
      (node (ref "U$1") (pin "6") (pinfunction "CANL_6") (pintype "bidirectional"))
    )
    (net (code "32") (name "CAN_RX") (class "Default")
      (node (ref "LS_BH_R") (pin "18") (pinfunction "B2_18") (pintype "bidirectional"))
      (node (ref "U$1") (pin "4") (pinfunction "RXD_4") (pintype "output"))
    )
    (net (code "33") (name "CAN_RX_3V") (class "Default")
      (node (ref "LS_BH_R") (pin "3") (pinfunction "A2_3") (pintype "bidirectional"))
      (node (ref "P9") (pin "24") (pinfunction "24_24") (pintype "passive"))
    )
    (net (code "34") (name "CAN_TX") (class "Default")
      (node (ref "LS_BH_R") (pin "20") (pinfunction "B1_20") (pintype "bidirectional"))
      (node (ref "U$1") (pin "1") (pinfunction "TXD_1") (pintype "input"))
    )
    (net (code "35") (name "CAN_TX_3V") (class "Default")
      (node (ref "LS_BH_R") (pin "1") (pinfunction "A1_1") (pintype "bidirectional"))
      (node (ref "P9") (pin "26") (pinfunction "26_26") (pintype "passive"))
    )
    (net (code "36") (name "GND") (class "Default")
      (node (ref "9AXIS-IMU") (pin "3") (pinfunction "3_3") (pintype "passive"))
      (node (ref "BALL-HANDLE_LEFT") (pin "1") (pinfunction "1_1") (pintype "passive"))
      (node (ref "BALL-HANDLE_RIGHT") (pin "1") (pinfunction "1_1") (pintype "passive"))
      (node (ref "C1") (pin "2") (pinfunction "2_2") (pintype "passive"))
      (node (ref "C10") (pin "2") (pinfunction "2_2") (pintype "passive"))
      (node (ref "C11") (pin "-") (pinfunction "-_-") (pintype "passive"))
      (node (ref "C12") (pin "-") (pinfunction "-_-") (pintype "passive"))
      (node (ref "C13") (pin "1") (pinfunction "1_1") (pintype "passive"))
      (node (ref "C14") (pin "1") (pinfunction "1_1") (pintype "passive"))
      (node (ref "C2") (pin "2") (pinfunction "2_2") (pintype "passive"))
      (node (ref "C3") (pin "2") (pinfunction "2_2") (pintype "passive"))
      (node (ref "C4") (pin "2") (pinfunction "2_2") (pintype "passive"))
      (node (ref "C5") (pin "2") (pinfunction "2_2") (pintype "passive"))
      (node (ref "C6") (pin "2") (pinfunction "2_2") (pintype "passive"))
      (node (ref "C7") (pin "2") (pinfunction "2_2") (pintype "passive"))
      (node (ref "C8") (pin "2") (pinfunction "2_2") (pintype "passive"))
      (node (ref "C9") (pin "2") (pinfunction "2_2") (pintype "passive"))
      (node (ref "CAN") (pin "1") (pinfunction "1_1") (pintype "passive"))
      (node (ref "IC1") (pin "4") (pinfunction "GND_4") (pintype "passive"))
      (node (ref "IC2") (pin "1") (pinfunction "ADJ_1") (pintype "input"))
      (node (ref "JST_LIGHTBARRIER") (pin "2") (pinfunction "2_2") (pintype "bidirectional"))
      (node (ref "JST_OPTICAL-FLOW") (pin "1") (pinfunction "1_1") (pintype "bidirectional"))
      (node (ref "JST_POTI1") (pin "2") (pinfunction "2_2") (pintype "bidirectional"))
      (node (ref "JST_POTI2") (pin "2") (pinfunction "2_2") (pintype "bidirectional"))
      (node (ref "JST_SERVO") (pin "2") (pinfunction "2_2") (pintype "bidirectional"))
      (node (ref "JST_SERVO2") (pin "2") (pinfunction "2_2") (pintype "bidirectional"))
      (node (ref "LS_BH") (pin "11") (pinfunction "GND_11") (pintype "passive"))
      (node (ref "LS_BH_R") (pin "11") (pinfunction "GND_11") (pintype "passive"))
      (node (ref "LS_OF") (pin "11") (pinfunction "GND_11") (pintype "passive"))
      (node (ref "NPN1") (pin "E") (pinfunction "E_E") (pintype "passive"))
      (node (ref "NPN2") (pin "E") (pinfunction "E_E") (pintype "passive"))
      (node (ref "NPN3") (pin "E") (pinfunction "E_E") (pintype "passive"))
      (node (ref "P8") (pin "1") (pinfunction "1_1") (pintype "passive"))
      (node (ref "P8") (pin "2") (pinfunction "2_2") (pintype "passive"))
      (node (ref "P9") (pin "1") (pinfunction "1_1") (pintype "passive"))
      (node (ref "P9") (pin "2") (pinfunction "2_2") (pintype "passive"))
      (node (ref "P9") (pin "34") (pinfunction "34_34") (pintype "passive"))
      (node (ref "P9") (pin "43") (pinfunction "43_43") (pintype "passive"))
      (node (ref "P9") (pin "44") (pinfunction "44_44") (pintype "passive"))
      (node (ref "P9") (pin "45") (pinfunction "45_45") (pintype "passive"))
      (node (ref "P9") (pin "46") (pinfunction "46_46") (pintype "passive"))
      (node (ref "POWER") (pin "2") (pinfunction "2_2") (pintype "bidirectional"))
      (node (ref "R1") (pin "1") (pinfunction "1_1") (pintype "passive"))
      (node (ref "R10") (pin "1") (pinfunction "1_1") (pintype "passive"))
      (node (ref "R11") (pin "1") (pinfunction "1_1") (pintype "passive"))
      (node (ref "R16") (pin "1") (pinfunction "1_1") (pintype "passive"))
      (node (ref "R17") (pin "1") (pinfunction "1_1") (pintype "passive"))
      (node (ref "R18") (pin "1") (pinfunction "1_1") (pintype "passive"))
      (node (ref "R19") (pin "1") (pinfunction "1_1") (pintype "passive"))
      (node (ref "R20") (pin "1") (pinfunction "1_1") (pintype "passive"))
      (node (ref "R21") (pin "1") (pinfunction "1_1") (pintype "passive"))
      (node (ref "R22") (pin "1") (pinfunction "1_1") (pintype "passive"))
      (node (ref "R5") (pin "1") (pinfunction "1_1") (pintype "passive"))
      (node (ref "R7") (pin "1") (pinfunction "1_1") (pintype "passive"))
      (node (ref "R9") (pin "1") (pinfunction "1_1") (pintype "passive"))
      (node (ref "SPI_EXTERN") (pin "6") (pinfunction "6_6") (pintype "passive"))
      (node (ref "STECKER_BOX") (pin "1") (pinfunction "1_1") (pintype "passive"))
      (node (ref "STECKER_BOX") (pin "2") (pinfunction "2_2") (pintype "passive"))
      (node (ref "U$1") (pin "2") (pinfunction "VSS_2") (pintype "passive"))
      (node (ref "X1") (pin "2") (pinfunction "KL_2") (pintype "passive"))
    )
    (net (code "37") (name "I2C2_SCL") (class "Default")
      (node (ref "P9") (pin "19") (pinfunction "19_19") (pintype "passive"))
      (node (ref "R29") (pin "1") (pinfunction "1_1") (pintype "passive"))
    )
    (net (code "38") (name "I2C2_SDA") (class "Default")
      (node (ref "P9") (pin "20") (pinfunction "20_20") (pintype "passive"))
      (node (ref "R30") (pin "1") (pinfunction "1_1") (pintype "passive"))
    )
    (net (code "39") (name "LB_ADC") (class "Default")
      (node (ref "JST_LIGHTBARRIER") (pin "3") (pinfunction "3_3") (pintype "bidirectional"))
      (node (ref "R24") (pin "2") (pinfunction "2_2") (pintype "passive"))
    )
    (net (code "40") (name "LB_ADC_1.8V") (class "Default")
      (node (ref "P9") (pin "40") (pinfunction "40_40") (pintype "passive"))
      (node (ref "R20") (pin "2") (pinfunction "2_2") (pintype "passive"))
      (node (ref "R24") (pin "1") (pinfunction "1_1") (pintype "passive"))
    )
    (net (code "41") (name "M_DRDY") (class "Default")
      (node (ref "9AXIS-IMU") (pin "6") (pinfunction "6_6") (pintype "passive"))
      (node (ref "P8") (pin "14") (pinfunction "14_14") (pintype "passive"))
    )
    (net (code "42") (name "Net-(9AXIS-IMU-Pad4)") (class "Default")
      (node (ref "9AXIS-IMU") (pin "4") (pinfunction "4_4") (pintype "passive"))
      (node (ref "R27") (pin "1") (pinfunction "1_1") (pintype "passive"))
      (node (ref "R29") (pin "2") (pinfunction "2_2") (pintype "passive"))
    )
    (net (code "43") (name "Net-(9AXIS-IMU-Pad5)") (class "Default")
      (node (ref "9AXIS-IMU") (pin "5") (pinfunction "5_5") (pintype "passive"))
      (node (ref "R28") (pin "1") (pinfunction "1_1") (pintype "passive"))
      (node (ref "R30") (pin "2") (pinfunction "2_2") (pintype "passive"))
    )
    (net (code "44") (name "Net-(CAN-Pad4)") (class "Default")
      (node (ref "CAN") (pin "4") (pinfunction "4_4") (pintype "passive"))
      (node (ref "SJ1") (pin "1") (pinfunction "1_1") (pintype "passive"))
    )
    (net (code "45") (name "Net-(IC1-VI)") (class "Default")
      (node (ref "C1") (pin "1") (pinfunction "1_1") (pintype "passive"))
      (node (ref "C11") (pin "+") (pinfunction "+_+") (pintype "passive"))
      (node (ref "C3") (pin "1") (pinfunction "1_1") (pintype "passive"))
      (node (ref "D1") (pin "C") (pinfunction "C_C") (pintype "passive"))
      (node (ref "D2") (pin "C") (pinfunction "C_C") (pintype "passive"))
      (node (ref "D3") (pin "C") (pinfunction "C_C") (pintype "passive"))
      (node (ref "IC1") (pin "1") (pinfunction "VI_1") (pintype "input"))
      (node (ref "IC2") (pin "3") (pinfunction "IN_3") (pintype "input"))
    )
    (net (code "46") (name "Net-(NPN1-PadC)") (class "Default")
      (node (ref "NPN1") (pin "C") (pinfunction "C_C") (pintype "passive"))
      (node (ref "PNP1") (pin "B") (pinfunction "B_B") (pintype "passive"))
      (node (ref "R13") (pin "1") (pinfunction "1_1") (pintype "passive"))
    )
    (net (code "47") (name "Net-(NPN2-PadC)") (class "Default")
      (node (ref "NPN2") (pin "C") (pinfunction "C_C") (pintype "passive"))
      (node (ref "PNP2") (pin "B") (pinfunction "B_B") (pintype "passive"))
      (node (ref "R14") (pin "1") (pinfunction "1_1") (pintype "passive"))
    )
    (net (code "48") (name "Net-(NPN3-PadC)") (class "Default")
      (node (ref "NPN3") (pin "C") (pinfunction "C_C") (pintype "passive"))
      (node (ref "PNP3") (pin "B") (pinfunction "B_B") (pintype "passive"))
      (node (ref "R15") (pin "1") (pinfunction "1_1") (pintype "passive"))
    )
    (net (code "49") (name "Net-(R2-Pad1)") (class "Default")
      (node (ref "R2") (pin "1") (pinfunction "1_1") (pintype "passive"))
      (node (ref "SJ2") (pin "1") (pinfunction "1_1") (pintype "passive"))
    )
    (net (code "50") (name "Net-(U$1-RS)") (class "Default")
      (node (ref "R1") (pin "2") (pinfunction "2_2") (pintype "passive"))
      (node (ref "U$1") (pin "8") (pinfunction "RS_8") (pintype "input"))
    )
    (net (code "51") (name "OF_NCS") (class "Default")
      (node (ref "JST_OPTICAL-FLOW") (pin "3") (pinfunction "3_3") (pintype "bidirectional"))
      (node (ref "LS_OF") (pin "20") (pinfunction "B1_20") (pintype "bidirectional"))
    )
    (net (code "52") (name "OF_NCS_3V") (class "Default")
      (node (ref "LS_OF") (pin "1") (pinfunction "A1_1") (pintype "bidirectional"))
      (node (ref "P9") (pin "30") (pinfunction "30_30") (pintype "passive"))
    )
    (net (code "53") (name "OF_NPD") (class "Default")
      (node (ref "JST_OPTICAL-FLOW") (pin "5") (pinfunction "5_5") (pintype "bidirectional"))
      (node (ref "LS_OF") (pin "17") (pinfunction "B3_17") (pintype "bidirectional"))
    )
    (net (code "54") (name "OF_NPD_3V") (class "Default")
      (node (ref "LS_OF") (pin "4") (pinfunction "A3_4") (pintype "bidirectional"))
      (node (ref "P9") (pin "25") (pinfunction "25_25") (pintype "passive"))
    )
    (net (code "55") (name "OF_RST") (class "Default")
      (node (ref "JST_OPTICAL-FLOW") (pin "7") (pinfunction "7_7") (pintype "bidirectional"))
      (node (ref "LS_OF") (pin "18") (pinfunction "B2_18") (pintype "bidirectional"))
    )
    (net (code "56") (name "OF_RST_3V") (class "Default")
      (node (ref "LS_OF") (pin "3") (pinfunction "A2_3") (pintype "bidirectional"))
      (node (ref "P9") (pin "27") (pinfunction "27_27") (pintype "passive"))
    )
    (net (code "57") (name "P_EOC") (class "Default")
      (node (ref "9AXIS-IMU") (pin "10") (pinfunction "10_10") (pintype "passive"))
      (node (ref "P8") (pin "26") (pinfunction "26_26") (pintype "passive"))
    )
    (net (code "58") (name "P_XCLR") (class "Default")
      (node (ref "9AXIS-IMU") (pin "9") (pinfunction "9_9") (pintype "passive"))
    )
    (net (code "59") (name "SERVO_PWM") (class "Default")
      (node (ref "JST_SERVO") (pin "3") (pinfunction "3_3") (pintype "bidirectional"))
      (node (ref "LS_BH_R") (pin "16") (pinfunction "B4_16") (pintype "bidirectional"))
    )
    (net (code "60") (name "SERVO_PWM2") (class "Default")
      (node (ref "JST_SERVO2") (pin "3") (pinfunction "3_3") (pintype "bidirectional"))
      (node (ref "LS_BH_R") (pin "17") (pinfunction "B3_17") (pintype "bidirectional"))
    )
    (net (code "61") (name "SERVO_PWM2_3V") (class "Default")
      (node (ref "LS_BH_R") (pin "4") (pinfunction "A3_4") (pintype "bidirectional"))
      (node (ref "P9") (pin "16") (pinfunction "16_16") (pintype "passive"))
    )
    (net (code "62") (name "SERVO_PWM_3V") (class "Default")
      (node (ref "LS_BH_R") (pin "5") (pinfunction "A4_5") (pintype "bidirectional"))
      (node (ref "P9") (pin "14") (pinfunction "14_14") (pintype "passive"))
    )
    (net (code "63") (name "SPI0_CLK") (class "Default")
      (node (ref "LS_OF") (pin "5") (pinfunction "A4_5") (pintype "bidirectional"))
      (node (ref "P9") (pin "22") (pinfunction "22_22") (pintype "passive"))
    )
    (net (code "64") (name "SPI0_CS") (class "Default")
      (node (ref "LS_OF") (pin "8") (pinfunction "A7_8") (pintype "bidirectional"))
      (node (ref "P9") (pin "17") (pinfunction "17_17") (pintype "passive"))
    )
    (net (code "65") (name "SPI0_D0_MISO") (class "Default")
      (node (ref "LS_OF") (pin "6") (pinfunction "A5_6") (pintype "bidirectional"))
      (node (ref "P9") (pin "21") (pinfunction "21_21") (pintype "passive"))
    )
    (net (code "66") (name "SPI0_D1_MOSI") (class "Default")
      (node (ref "LS_OF") (pin "7") (pinfunction "A6_7") (pintype "bidirectional"))
      (node (ref "P9") (pin "18") (pinfunction "18_18") (pintype "passive"))
    )
    (net (code "67") (name "SPI_CLK") (class "Default")
      (node (ref "JST_OPTICAL-FLOW") (pin "6") (pinfunction "6_6") (pintype "bidirectional"))
      (node (ref "LS_OF") (pin "16") (pinfunction "B4_16") (pintype "bidirectional"))
      (node (ref "SPI_EXTERN") (pin "3") (pinfunction "3_3") (pintype "passive"))
    )
    (net (code "68") (name "SPI_CS") (class "Default")
      (node (ref "LS_OF") (pin "13") (pinfunction "B7_13") (pintype "bidirectional"))
      (node (ref "SPI_EXTERN") (pin "5") (pinfunction "5_5") (pintype "passive"))
    )
    (net (code "69") (name "SPI_MISO") (class "Default")
      (node (ref "JST_OPTICAL-FLOW") (pin "4") (pinfunction "4_4") (pintype "bidirectional"))
      (node (ref "LS_OF") (pin "15") (pinfunction "B5_15") (pintype "bidirectional"))
      (node (ref "SPI_EXTERN") (pin "1") (pinfunction "1_1") (pintype "passive"))
    )
    (net (code "70") (name "SPI_MOSI") (class "Default")
      (node (ref "JST_OPTICAL-FLOW") (pin "2") (pinfunction "2_2") (pintype "bidirectional"))
      (node (ref "LS_OF") (pin "14") (pinfunction "B6_14") (pintype "bidirectional"))
      (node (ref "SPI_EXTERN") (pin "4") (pinfunction "4_4") (pintype "passive"))
    )
    (net (code "71") (name "SW_BUNDLE-LED") (class "Default")
      (node (ref "PNP2") (pin "C") (pinfunction "C_C") (pintype "passive"))
      (node (ref "STECKER_BOX") (pin "8") (pinfunction "8_8") (pintype "passive"))
    )
    (net (code "72") (name "SW_BUNDLE-LED_3V") (class "Default")
      (node (ref "NPN2") (pin "B") (pinfunction "B_B") (pintype "passive"))
      (node (ref "P9") (pin "23") (pinfunction "23_23") (pintype "passive"))
      (node (ref "R17") (pin "2") (pinfunction "2_2") (pintype "passive"))
    )
    (net (code "73") (name "SW_BUNDLE_3V") (class "Default")
      (node (ref "P9") (pin "13") (pinfunction "13_13") (pintype "passive"))
      (node (ref "STECKER_BOX") (pin "7") (pinfunction "7_7") (pintype "passive"))
    )
    (net (code "74") (name "SW_POWER-LED") (class "Default")
      (node (ref "PNP3") (pin "C") (pinfunction "C_C") (pintype "passive"))
      (node (ref "STECKER_BOX") (pin "10") (pinfunction "10_10") (pintype "passive"))
    )
    (net (code "75") (name "SW_POWER-LED_3V") (class "Default")
      (node (ref "NPN3") (pin "B") (pinfunction "B_B") (pintype "passive"))
      (node (ref "P9") (pin "42") (pinfunction "42_42") (pintype "passive"))
      (node (ref "R16") (pin "2") (pinfunction "2_2") (pintype "passive"))
    )
    (net (code "76") (name "SW_PWR_BUT") (class "Default")
      (node (ref "P9") (pin "9") (pinfunction "9_9") (pintype "passive"))
      (node (ref "STECKER_BOX") (pin "9") (pinfunction "9_9") (pintype "passive"))
    )
    (net (code "77") (name "SW_VISION-LED") (class "Default")
      (node (ref "PNP1") (pin "C") (pinfunction "C_C") (pintype "passive"))
      (node (ref "STECKER_BOX") (pin "6") (pinfunction "6_6") (pintype "passive"))
    )
    (net (code "78") (name "SW_VISION-LED_3V") (class "Default")
      (node (ref "NPN1") (pin "B") (pinfunction "B_B") (pintype "passive"))
      (node (ref "P9") (pin "15") (pinfunction "15_15") (pintype "passive"))
      (node (ref "R18") (pin "2") (pinfunction "2_2") (pintype "passive"))
    )
    (net (code "79") (name "SW_VISION_3V") (class "Default")
      (node (ref "P9") (pin "11") (pinfunction "11_11") (pintype "passive"))
      (node (ref "STECKER_BOX") (pin "5") (pinfunction "5_5") (pintype "passive"))
    )
    (net (code "80") (name "T_INT1") (class "Default")
      (node (ref "9AXIS-IMU") (pin "8") (pinfunction "8_8") (pintype "passive"))
      (node (ref "P8") (pin "18") (pinfunction "18_18") (pintype "passive"))
    )
    (net (code "81") (name "unconnected-(9AXIS-IMU-Pad1)") (class "Default")
      (node (ref "9AXIS-IMU") (pin "1") (pinfunction "1_1") (pintype "passive"))
    )
    (net (code "82") (name "unconnected-(BALL-HANDLE_LEFT-Pad7)") (class "Default")
      (node (ref "BALL-HANDLE_LEFT") (pin "7") (pinfunction "7_7") (pintype "passive"))
    )
    (net (code "83") (name "unconnected-(BALL-HANDLE_LEFT-Pad8)") (class "Default")
      (node (ref "BALL-HANDLE_LEFT") (pin "8") (pinfunction "8_8") (pintype "passive"))
    )
    (net (code "84") (name "unconnected-(BALL-HANDLE_RIGHT-Pad7)") (class "Default")
      (node (ref "BALL-HANDLE_RIGHT") (pin "7") (pinfunction "7_7") (pintype "passive"))
    )
    (net (code "85") (name "unconnected-(BALL-HANDLE_RIGHT-Pad8)") (class "Default")
      (node (ref "BALL-HANDLE_RIGHT") (pin "8") (pinfunction "8_8") (pintype "passive"))
    )
    (net (code "86") (name "unconnected-(LS_BH-A7-Pad8)") (class "Default")
      (node (ref "LS_BH") (pin "8") (pinfunction "A7_8") (pintype "bidirectional"))
    )
    (net (code "87") (name "unconnected-(LS_BH-A8-Pad9)") (class "Default")
      (node (ref "LS_BH") (pin "9") (pinfunction "A8_9") (pintype "bidirectional"))
    )
    (net (code "88") (name "unconnected-(LS_BH-B7-Pad13)") (class "Default")
      (node (ref "LS_BH") (pin "13") (pinfunction "B7_13") (pintype "bidirectional"))
    )
    (net (code "89") (name "unconnected-(LS_BH-B8-Pad12)") (class "Default")
      (node (ref "LS_BH") (pin "12") (pinfunction "B8_12") (pintype "bidirectional"))
    )
    (net (code "90") (name "unconnected-(LS_BH_R-A5-Pad6)") (class "Default")
      (node (ref "LS_BH_R") (pin "6") (pinfunction "A5_6") (pintype "bidirectional"))
    )
    (net (code "91") (name "unconnected-(LS_BH_R-A6-Pad7)") (class "Default")
      (node (ref "LS_BH_R") (pin "7") (pinfunction "A6_7") (pintype "bidirectional"))
    )
    (net (code "92") (name "unconnected-(LS_BH_R-A7-Pad8)") (class "Default")
      (node (ref "LS_BH_R") (pin "8") (pinfunction "A7_8") (pintype "bidirectional"))
    )
    (net (code "93") (name "unconnected-(LS_BH_R-A8-Pad9)") (class "Default")
      (node (ref "LS_BH_R") (pin "9") (pinfunction "A8_9") (pintype "bidirectional"))
    )
    (net (code "94") (name "unconnected-(LS_BH_R-B5-Pad15)") (class "Default")
      (node (ref "LS_BH_R") (pin "15") (pinfunction "B5_15") (pintype "bidirectional"))
    )
    (net (code "95") (name "unconnected-(LS_BH_R-B6-Pad14)") (class "Default")
      (node (ref "LS_BH_R") (pin "14") (pinfunction "B6_14") (pintype "bidirectional"))
    )
    (net (code "96") (name "unconnected-(LS_BH_R-B7-Pad13)") (class "Default")
      (node (ref "LS_BH_R") (pin "13") (pinfunction "B7_13") (pintype "bidirectional"))
    )
    (net (code "97") (name "unconnected-(LS_BH_R-B8-Pad12)") (class "Default")
      (node (ref "LS_BH_R") (pin "12") (pinfunction "B8_12") (pintype "bidirectional"))
    )
    (net (code "98") (name "unconnected-(LS_OF-A8-Pad9)") (class "Default")
      (node (ref "LS_OF") (pin "9") (pinfunction "A8_9") (pintype "bidirectional"))
    )
    (net (code "99") (name "unconnected-(LS_OF-B8-Pad12)") (class "Default")
      (node (ref "LS_OF") (pin "12") (pinfunction "B8_12") (pintype "bidirectional"))
    )
    (net (code "100") (name "unconnected-(P8-Pad3)") (class "Default")
      (node (ref "P8") (pin "3") (pinfunction "3_3") (pintype "passive"))
    )
    (net (code "101") (name "unconnected-(P8-Pad4)") (class "Default")
      (node (ref "P8") (pin "4") (pinfunction "4_4") (pintype "passive"))
    )
    (net (code "102") (name "unconnected-(P8-Pad5)") (class "Default")
      (node (ref "P8") (pin "5") (pinfunction "5_5") (pintype "passive"))
    )
    (net (code "103") (name "unconnected-(P8-Pad6)") (class "Default")
      (node (ref "P8") (pin "6") (pinfunction "6_6") (pintype "passive"))
    )
    (net (code "104") (name "unconnected-(P8-Pad20)") (class "Default")
      (node (ref "P8") (pin "20") (pinfunction "20_20") (pintype "passive"))
    )
    (net (code "105") (name "unconnected-(P8-Pad21)") (class "Default")
      (node (ref "P8") (pin "21") (pinfunction "21_21") (pintype "passive"))
    )
    (net (code "106") (name "unconnected-(P8-Pad22)") (class "Default")
      (node (ref "P8") (pin "22") (pinfunction "22_22") (pintype "passive"))
    )
    (net (code "107") (name "unconnected-(P8-Pad23)") (class "Default")
      (node (ref "P8") (pin "23") (pinfunction "23_23") (pintype "passive"))
    )
    (net (code "108") (name "unconnected-(P8-Pad24)") (class "Default")
      (node (ref "P8") (pin "24") (pinfunction "24_24") (pintype "passive"))
    )
    (net (code "109") (name "unconnected-(P8-Pad25)") (class "Default")
      (node (ref "P8") (pin "25") (pinfunction "25_25") (pintype "passive"))
    )
    (net (code "110") (name "unconnected-(P8-Pad27)") (class "Default")
      (node (ref "P8") (pin "27") (pinfunction "27_27") (pintype "passive"))
    )
    (net (code "111") (name "unconnected-(P8-Pad28)") (class "Default")
      (node (ref "P8") (pin "28") (pinfunction "28_28") (pintype "passive"))
    )
    (net (code "112") (name "unconnected-(P8-Pad29)") (class "Default")
      (node (ref "P8") (pin "29") (pinfunction "29_29") (pintype "passive"))
    )
    (net (code "113") (name "unconnected-(P8-Pad30)") (class "Default")
      (node (ref "P8") (pin "30") (pinfunction "30_30") (pintype "passive"))
    )
    (net (code "114") (name "unconnected-(P8-Pad31)") (class "Default")
      (node (ref "P8") (pin "31") (pinfunction "31_31") (pintype "passive"))
    )
    (net (code "115") (name "unconnected-(P8-Pad32)") (class "Default")
      (node (ref "P8") (pin "32") (pinfunction "32_32") (pintype "passive"))
    )
    (net (code "116") (name "unconnected-(P8-Pad33)") (class "Default")
      (node (ref "P8") (pin "33") (pinfunction "33_33") (pintype "passive"))
    )
    (net (code "117") (name "unconnected-(P8-Pad34)") (class "Default")
      (node (ref "P8") (pin "34") (pinfunction "34_34") (pintype "passive"))
    )
    (net (code "118") (name "unconnected-(P8-Pad35)") (class "Default")
      (node (ref "P8") (pin "35") (pinfunction "35_35") (pintype "passive"))
    )
    (net (code "119") (name "unconnected-(P8-Pad36)") (class "Default")
      (node (ref "P8") (pin "36") (pinfunction "36_36") (pintype "passive"))
    )
    (net (code "120") (name "unconnected-(P8-Pad37)") (class "Default")
      (node (ref "P8") (pin "37") (pinfunction "37_37") (pintype "passive"))
    )
    (net (code "121") (name "unconnected-(P8-Pad38)") (class "Default")
      (node (ref "P8") (pin "38") (pinfunction "38_38") (pintype "passive"))
    )
    (net (code "122") (name "unconnected-(P8-Pad39)") (class "Default")
      (node (ref "P8") (pin "39") (pinfunction "39_39") (pintype "passive"))
    )
    (net (code "123") (name "unconnected-(P8-Pad40)") (class "Default")
      (node (ref "P8") (pin "40") (pinfunction "40_40") (pintype "passive"))
    )
    (net (code "124") (name "unconnected-(P8-Pad41)") (class "Default")
      (node (ref "P8") (pin "41") (pinfunction "41_41") (pintype "passive"))
    )
    (net (code "125") (name "unconnected-(P8-Pad42)") (class "Default")
      (node (ref "P8") (pin "42") (pinfunction "42_42") (pintype "passive"))
    )
    (net (code "126") (name "unconnected-(P8-Pad43)") (class "Default")
      (node (ref "P8") (pin "43") (pinfunction "43_43") (pintype "passive"))
    )
    (net (code "127") (name "unconnected-(P8-Pad44)") (class "Default")
      (node (ref "P8") (pin "44") (pinfunction "44_44") (pintype "passive"))
    )
    (net (code "128") (name "unconnected-(P8-Pad45)") (class "Default")
      (node (ref "P8") (pin "45") (pinfunction "45_45") (pintype "passive"))
    )
    (net (code "129") (name "unconnected-(P8-Pad46)") (class "Default")
      (node (ref "P8") (pin "46") (pinfunction "46_46") (pintype "passive"))
    )
    (net (code "130") (name "unconnected-(P9-Pad7)") (class "Default")
      (node (ref "P9") (pin "7") (pinfunction "7_7") (pintype "passive"))
    )
    (net (code "131") (name "unconnected-(P9-Pad8)") (class "Default")
      (node (ref "P9") (pin "8") (pinfunction "8_8") (pintype "passive"))
    )
    (net (code "132") (name "unconnected-(P9-Pad10)") (class "Default")
      (node (ref "P9") (pin "10") (pinfunction "10_10") (pintype "passive"))
    )
    (net (code "133") (name "unconnected-(P9-Pad12)") (class "Default")
      (node (ref "P9") (pin "12") (pinfunction "12_12") (pintype "passive"))
    )
    (net (code "134") (name "unconnected-(P9-Pad28)") (class "Default")
      (node (ref "P9") (pin "28") (pinfunction "28_28") (pintype "passive"))
    )
    (net (code "135") (name "unconnected-(P9-Pad29)") (class "Default")
      (node (ref "P9") (pin "29") (pinfunction "29_29") (pintype "passive"))
    )
    (net (code "136") (name "unconnected-(P9-Pad31)") (class "Default")
      (node (ref "P9") (pin "31") (pinfunction "31_31") (pintype "passive"))
    )
    (net (code "137") (name "unconnected-(P9-Pad32)") (class "Default")
      (node (ref "P9") (pin "32") (pinfunction "32_32") (pintype "passive"))
    )
    (net (code "138") (name "unconnected-(P9-Pad35)") (class "Default")
      (node (ref "P9") (pin "35") (pinfunction "35_35") (pintype "passive"))
    )
    (net (code "139") (name "unconnected-(P9-Pad36)") (class "Default")
      (node (ref "P9") (pin "36") (pinfunction "36_36") (pintype "passive"))
    )
    (net (code "140") (name "unconnected-(P9-Pad41)") (class "Default")
      (node (ref "P9") (pin "41") (pinfunction "41_41") (pintype "passive"))
    )
    (net (code "141") (name "unconnected-(STECKER_BOX-Pad3)") (class "Default")
      (node (ref "STECKER_BOX") (pin "3") (pinfunction "3_3") (pintype "passive"))
    )
    (net (code "142") (name "unconnected-(STECKER_BOX-Pad4)") (class "Default")
      (node (ref "STECKER_BOX") (pin "4") (pinfunction "4_4") (pintype "passive"))
    )
    (net (code "143") (name "unconnected-(U$1-VREF-Pad5)") (class "Default")
      (node (ref "U$1") (pin "5") (pinfunction "VREF_5") (pintype "output"))
    )
    (net (code "144") (name "~{BH_L_RESET_3V}") (class "Default")
      (node (ref "LS_BH") (pin "4") (pinfunction "A3_4") (pintype "bidirectional"))
      (node (ref "P8") (pin "11") (pinfunction "11_11") (pintype "passive"))
    )
    (net (code "145") (name "~{BH_L_RESET}") (class "Default")
      (node (ref "BALL-HANDLE_LEFT") (pin "4") (pinfunction "4_4") (pintype "passive"))
      (node (ref "LS_BH") (pin "17") (pinfunction "B3_17") (pintype "bidirectional"))
    )
    (net (code "146") (name "~{BH_R_RESET_3V}") (class "Default")
      (node (ref "LS_BH") (pin "7") (pinfunction "A6_7") (pintype "bidirectional"))
      (node (ref "P8") (pin "7") (pinfunction "7_7") (pintype "passive"))
    )
    (net (code "147") (name "~{BH_R_RESET}") (class "Default")
      (node (ref "BALL-HANDLE_RIGHT") (pin "4") (pinfunction "4_4") (pintype "passive"))
      (node (ref "LS_BH") (pin "14") (pinfunction "B6_14") (pintype "bidirectional"))
    )
  )
)
